# Sheet1.net
KiCad netlist of a schematic drawn in Altium Designer
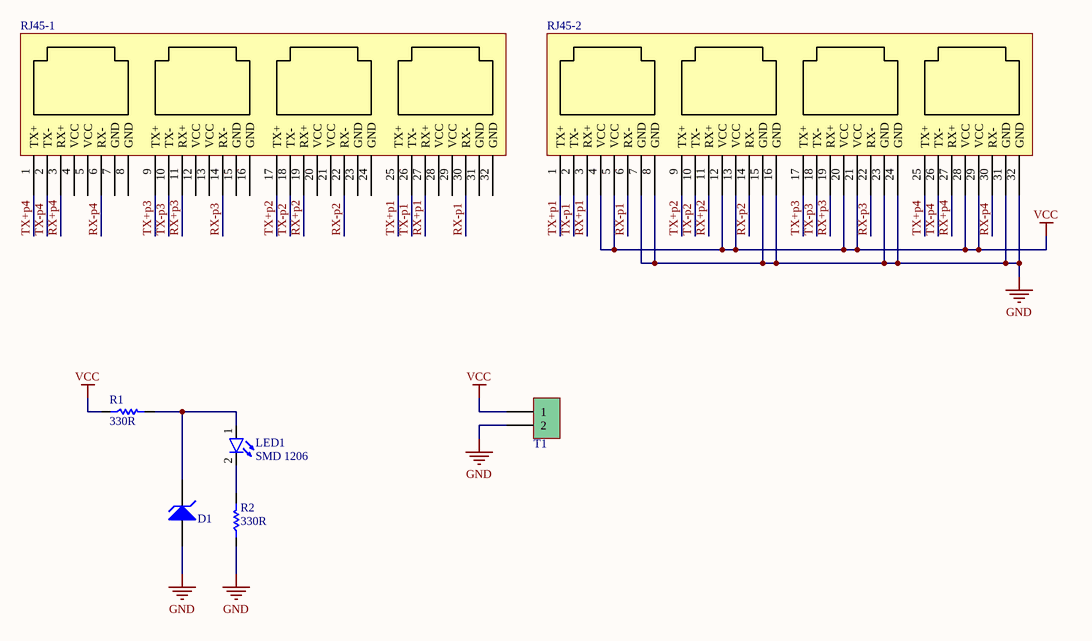
[diagram p0: Sheet1.SchDoc]

(export (version "E")
  (design (tool "Eeschema 10.0.6"))
  (components
    (comp (ref "D1")
      (value "Diode Zener")
      (footprint "Diode 1W")
      (description "Zener Diode")
      (fields (field (name "VOLTAGE") "12V") (field (name "DESIGNER") "Saeid Jorablo"))
      (libsource (lib "Electrovolt Lib") (part "Diode Zener"))
    )
    (comp (ref "LED1")
      (value "Red")
      (footprint "LED-5mm")
      (description "LED")
      (fields (field (name "SIZE") "SMD 1206") (field (name "DESIGNER") "Saeid Jorablo"))
      (libsource (lib "Electrovolt Lib") (part "LED"))
    )
    (comp (ref "R1")
      (value "330R")
      (footprint "RES 1206 (3216X08L)")
      (description "Resistor")
      (fields (field (name "TOLERANCE") "5%") (field (name "POWER") "1/8 W"))
      (libsource (lib "Electrovolt Lib") (part "Resistor"))
    )
    (comp (ref "R2")
      (value "330R")
      (footprint "RES 1206 (3216X08L)")
      (description "Resistor")
      (fields (field (name "TOLERANCE") "5%") (field (name "POWER") "1/8 W"))
      (libsource (lib "Electrovolt Lib") (part "Resistor"))
    )
    (comp (ref "RJ45-1") (value "~") (footprint "rj45-w57-4") (libsource (lib "Schlib1") (part "RJ45-w57-4")))
    (comp (ref "RJ45-2") (value "~") (footprint "rj45-w57-4") (libsource (lib "Schlib1") (part "RJ45-w57-4")))
    (comp (ref "T1")
      (value "Phoenix terminal")
      (footprint "phoenix terminal 2")
      (description "Terminal 2 Pin")
      (fields (field (name "DESIGNER") "Seyed Mohsen Ghasemain") (field (name "E-MAIL") "picpars@gmail.com"))
      (libsource (lib "usefully_Library") (part "Phoenix terminal 2"))
    )
  )
  (nets
    (net (code "1") (name "/RX+p1") (class "Default")
      (node (ref "RJ45-1") (pin "27") (pinfunction "RX+_27") (pintype "passive"))
      (node (ref "RJ45-2") (pin "3") (pinfunction "RX+_3") (pintype "passive"))
    )
    (net (code "2") (name "/RX+p2") (class "Default")
      (node (ref "RJ45-1") (pin "19") (pinfunction "RX+_19") (pintype "passive"))
      (node (ref "RJ45-2") (pin "11") (pinfunction "RX+_11") (pintype "passive"))
    )
    (net (code "3") (name "/RX+p3") (class "Default")
      (node (ref "RJ45-1") (pin "11") (pinfunction "RX+_11") (pintype "passive"))
      (node (ref "RJ45-2") (pin "19") (pinfunction "RX+_19") (pintype "passive"))
    )
    (net (code "4") (name "/RX+p4") (class "Default")
      (node (ref "RJ45-1") (pin "3") (pinfunction "RX+_3") (pintype "passive"))
      (node (ref "RJ45-2") (pin "27") (pinfunction "RX+_27") (pintype "passive"))
    )
    (net (code "5") (name "/RX-p1") (class "Default")
      (node (ref "RJ45-1") (pin "30") (pinfunction "RX-_30") (pintype "passive"))
      (node (ref "RJ45-2") (pin "6") (pinfunction "RX-_6") (pintype "passive"))
    )
    (net (code "6") (name "/RX-p2") (class "Default")
      (node (ref "RJ45-1") (pin "22") (pinfunction "RX-_22") (pintype "passive"))
      (node (ref "RJ45-2") (pin "14") (pinfunction "RX-_14") (pintype "passive"))
    )
    (net (code "7") (name "/RX-p3") (class "Default")
      (node (ref "RJ45-1") (pin "14") (pinfunction "RX-_14") (pintype "passive"))
      (node (ref "RJ45-2") (pin "22") (pinfunction "RX-_22") (pintype "passive"))
    )
    (net (code "8") (name "/RX-p4") (class "Default")
      (node (ref "RJ45-1") (pin "6") (pinfunction "RX-_6") (pintype "passive"))
      (node (ref "RJ45-2") (pin "30") (pinfunction "RX-_30") (pintype "passive"))
    )
    (net (code "9") (name "/TX+p1") (class "Default")
      (node (ref "RJ45-1") (pin "25") (pinfunction "TX+_25") (pintype "passive"))
      (node (ref "RJ45-2") (pin "1") (pinfunction "TX+_1") (pintype "passive"))
    )
    (net (code "10") (name "/TX+p2") (class "Default")
      (node (ref "RJ45-1") (pin "17") (pinfunction "TX+_17") (pintype "passive"))
      (node (ref "RJ45-2") (pin "9") (pinfunction "TX+_9") (pintype "passive"))
    )
    (net (code "11") (name "/TX+p3") (class "Default")
      (node (ref "RJ45-1") (pin "9") (pinfunction "TX+_9") (pintype "passive"))
      (node (ref "RJ45-2") (pin "17") (pinfunction "TX+_17") (pintype "passive"))
    )
    (net (code "12") (name "/TX+p4") (class "Default")
      (node (ref "RJ45-1") (pin "1") (pinfunction "TX+_1") (pintype "passive"))
      (node (ref "RJ45-2") (pin "25") (pinfunction "TX+_25") (pintype "passive"))
    )
    (net (code "13") (name "/TX-p1") (class "Default")
      (node (ref "RJ45-1") (pin "26") (pinfunction "TX-_26") (pintype "passive"))
      (node (ref "RJ45-2") (pin "2") (pinfunction "TX-_2") (pintype "passive"))
    )
    (net (code "14") (name "/TX-p2") (class "Default")
      (node (ref "RJ45-1") (pin "18") (pinfunction "TX-_18") (pintype "passive"))
      (node (ref "RJ45-2") (pin "10") (pinfunction "TX-_10") (pintype "passive"))
    )
    (net (code "15") (name "/TX-p3") (class "Default")
      (node (ref "RJ45-1") (pin "10") (pinfunction "TX-_10") (pintype "passive"))
      (node (ref "RJ45-2") (pin "18") (pinfunction "TX-_18") (pintype "passive"))
    )
    (net (code "16") (name "/TX-p4") (class "Default")
      (node (ref "RJ45-1") (pin "2") (pinfunction "TX-_2") (pintype "passive"))
      (node (ref "RJ45-2") (pin "26") (pinfunction "TX-_26") (pintype "passive"))
    )
    (net (code "17") (name "GND") (class "Default")
      (node (ref "D1") (pin "1") (pinfunction "A_1") (pintype "passive"))
      (node (ref "R2") (pin "1") (pinfunction "1_1") (pintype "passive"))
      (node (ref "RJ45-2") (pin "15") (pinfunction "GND_15") (pintype "passive"))
      (node (ref "RJ45-2") (pin "16") (pinfunction "GND_16") (pintype "passive"))
      (node (ref "RJ45-2") (pin "23") (pinfunction "GND_23") (pintype "passive"))
      (node (ref "RJ45-2") (pin "24") (pinfunction "GND_24") (pintype "passive"))
      (node (ref "RJ45-2") (pin "31") (pinfunction "GND_31") (pintype "passive"))
      (node (ref "RJ45-2") (pin "32") (pinfunction "GND_32") (pintype "passive"))
      (node (ref "RJ45-2") (pin "7") (pinfunction "GND_7") (pintype "passive"))
      (node (ref "RJ45-2") (pin "8") (pinfunction "GND_8") (pintype "passive"))
      (node (ref "T1") (pin "2") (pinfunction "2_2") (pintype "passive"))
    )
    (net (code "18") (name "Net-(D1-K)") (class "Default")
      (node (ref "D1") (pin "2") (pinfunction "K_2") (pintype "passive"))
      (node (ref "LED1") (pin "1") (pinfunction "A_1") (pintype "passive"))
      (node (ref "R1") (pin "2") (pinfunction "2_2") (pintype "passive"))
    )
    (net (code "19") (name "Net-(LED1-K)") (class "Default")
      (node (ref "LED1") (pin "2") (pinfunction "K_2") (pintype "passive"))
      (node (ref "R2") (pin "2") (pinfunction "2_2") (pintype "passive"))
    )
    (net (code "20") (name "VCC") (class "Default")
      (node (ref "R1") (pin "1") (pinfunction "1_1") (pintype "passive"))
      (node (ref "RJ45-2") (pin "12") (pinfunction "VCC_12") (pintype "passive"))
      (node (ref "RJ45-2") (pin "13") (pinfunction "VCC_13") (pintype "passive"))
      (node (ref "RJ45-2") (pin "20") (pinfunction "VCC_20") (pintype "passive"))
      (node (ref "RJ45-2") (pin "21") (pinfunction "VCC_21") (pintype "passive"))
      (node (ref "RJ45-2") (pin "28") (pinfunction "VCC_28") (pintype "passive"))
      (node (ref "RJ45-2") (pin "29") (pinfunction "VCC_29") (pintype "passive"))
      (node (ref "RJ45-2") (pin "4") (pinfunction "VCC_4") (pintype "passive"))
      (node (ref "RJ45-2") (pin "5") (pinfunction "VCC_5") (pintype "passive"))
      (node (ref "T1") (pin "1") (pinfunction "1_1") (pintype "passive"))
    )
    (net (code "21") (name "unconnected-(RJ45-1-GND-Pad7)") (class "Default")
      (node (ref "RJ45-1") (pin "7") (pinfunction "GND_7") (pintype "passive"))
    )
    (net (code "22") (name "unconnected-(RJ45-1-GND-Pad8)") (class "Default")
      (node (ref "RJ45-1") (pin "8") (pinfunction "GND_8") (pintype "passive"))
    )
    (net (code "23") (name "unconnected-(RJ45-1-GND-Pad15)") (class "Default")
      (node (ref "RJ45-1") (pin "15") (pinfunction "GND_15") (pintype "passive"))
    )
    (net (code "24") (name "unconnected-(RJ45-1-GND-Pad16)") (class "Default")
      (node (ref "RJ45-1") (pin "16") (pinfunction "GND_16") (pintype "passive"))
    )
    (net (code "25") (name "unconnected-(RJ45-1-GND-Pad23)") (class "Default")
      (node (ref "RJ45-1") (pin "23") (pinfunction "GND_23") (pintype "passive"))
    )
    (net (code "26") (name "unconnected-(RJ45-1-GND-Pad24)") (class "Default")
      (node (ref "RJ45-1") (pin "24") (pinfunction "GND_24") (pintype "passive"))
    )
    (net (code "27") (name "unconnected-(RJ45-1-GND-Pad31)") (class "Default")
      (node (ref "RJ45-1") (pin "31") (pinfunction "GND_31") (pintype "passive"))
    )
    (net (code "28") (name "unconnected-(RJ45-1-GND-Pad32)") (class "Default")
      (node (ref "RJ45-1") (pin "32") (pinfunction "GND_32") (pintype "passive"))
    )
    (net (code "29") (name "unconnected-(RJ45-1-VCC-Pad4)") (class "Default")
      (node (ref "RJ45-1") (pin "4") (pinfunction "VCC_4") (pintype "passive"))
    )
    (net (code "30") (name "unconnected-(RJ45-1-VCC-Pad5)") (class "Default")
      (node (ref "RJ45-1") (pin "5") (pinfunction "VCC_5") (pintype "passive"))
    )
    (net (code "31") (name "unconnected-(RJ45-1-VCC-Pad12)") (class "Default")
      (node (ref "RJ45-1") (pin "12") (pinfunction "VCC_12") (pintype "passive"))
    )
    (net (code "32") (name "unconnected-(RJ45-1-VCC-Pad13)") (class "Default")
      (node (ref "RJ45-1") (pin "13") (pinfunction "VCC_13") (pintype "passive"))
    )
    (net (code "33") (name "unconnected-(RJ45-1-VCC-Pad20)") (class "Default")
      (node (ref "RJ45-1") (pin "20") (pinfunction "VCC_20") (pintype "passive"))
    )
    (net (code "34") (name "unconnected-(RJ45-1-VCC-Pad21)") (class "Default")
      (node (ref "RJ45-1") (pin "21") (pinfunction "VCC_21") (pintype "passive"))
    )
    (net (code "35") (name "unconnected-(RJ45-1-VCC-Pad28)") (class "Default")
      (node (ref "RJ45-1") (pin "28") (pinfunction "VCC_28") (pintype "passive"))
    )
    (net (code "36") (name "unconnected-(RJ45-1-VCC-Pad29)") (class "Default")
      (node (ref "RJ45-1") (pin "29") (pinfunction "VCC_29") (pintype "passive"))
    )
  )
)
